# ACNodeShield.net
KiCad netlist of a schematic drawn in EAGLE
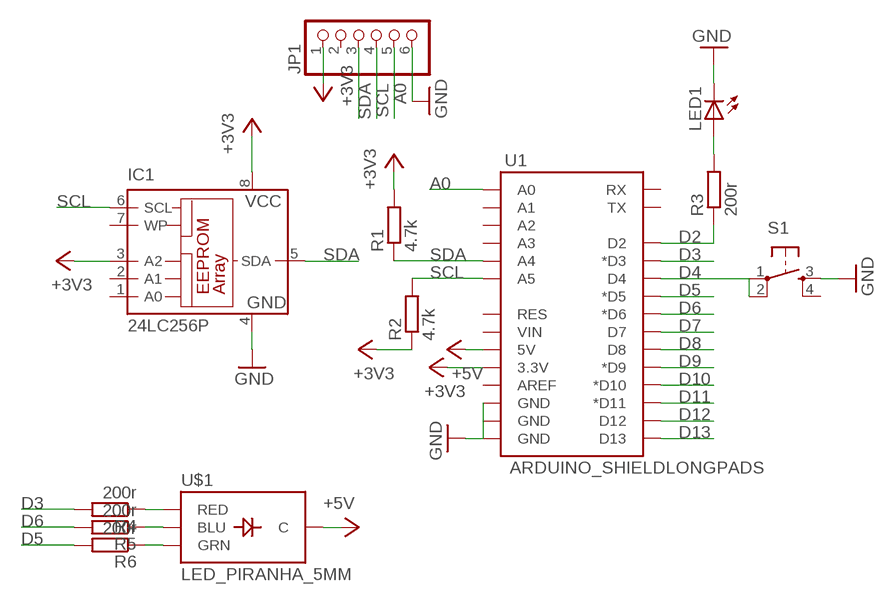
[diagram p0: schematic, sheet 1]

(export (version "E")
  (design (tool "Eeschema 10.0.6"))
  (components
    (comp (ref "IC1")
      (value "24LC256P")
      (footprint "eagle-import:DIL8")
      (fields (field (name "MF") "MICROCHIP") (field (name "MPN") "24LC256-E/P"))
      (libsource (lib "eagle-import") (part "24PLC256"))
    )
    (comp (ref "JP1")
      (value "PINHD-1X6")
      (footprint "eagle-import:1X06")
      (libsource (lib "eagle-import") (part "PINHD-1X6"))
    )
    (comp (ref "LED1")
      (value "LED5MM")
      (footprint "eagle-import:LED5MM")
      (libsource (lib "eagle-import") (part "LED5MM"))
    )
    (comp (ref "R1")
      (value "4.7k")
      (footprint "eagle-import:0204_7")
      (libsource (lib "eagle-import") (part "R-EU_0204/7"))
    )
    (comp (ref "R2")
      (value "4.7k")
      (footprint "eagle-import:0204_7")
      (libsource (lib "eagle-import") (part "R-EU_0204/7"))
    )
    (comp (ref "R3")
      (value "200r")
      (footprint "eagle-import:0204_7")
      (libsource (lib "eagle-import") (part "R-EU_0204/7"))
    )
    (comp (ref "R4")
      (value "200r")
      (footprint "eagle-import:0204_7")
      (libsource (lib "eagle-import") (part "R-EU_0204/7"))
    )
    (comp (ref "R5")
      (value "200r")
      (footprint "eagle-import:0204_7")
      (libsource (lib "eagle-import") (part "R-EU_0204/7"))
    )
    (comp (ref "R6")
      (value "200r")
      (footprint "eagle-import:0204_7")
      (libsource (lib "eagle-import") (part "R-EU_0204/7"))
    )
    (comp (ref "S1")
      (value "TAC_SWITCHPTH")
      (footprint "eagle-import:TACTILE-PTH")
      (libsource (lib "eagle-import") (part "TAC_SWITCHPTH"))
    )
    (comp (ref "U$1")
      (value "LED_PIRANHA_5MM")
      (footprint "eagle-import:LED_PIRANHA_5MM")
      (libsource (lib "eagle-import") (part "LED_PIRANHA_5MM"))
    )
    (comp (ref "U1")
      (value "ARDUINO_SHIELDLONGPADS")
      (footprint "eagle-import:DUEMILANOVE_SHIELD_LONGPADS")
      (libsource (lib "eagle-import") (part "ARDUINO_SHIELDLONGPADS"))
    )
  )
  (nets
    (net (code "1") (name "+3V3") (class "Default")
      (node (ref "IC1") (pin "3") (pinfunction "A2_3") (pintype "input"))
      (node (ref "IC1") (pin "8") (pinfunction "VCC_8") (pintype "power_in"))
      (node (ref "JP1") (pin "1") (pinfunction "1_1") (pintype "passive"))
      (node (ref "R1") (pin "2") (pinfunction "2_2") (pintype "passive"))
      (node (ref "R2") (pin "1") (pinfunction "1_1") (pintype "passive"))
      (node (ref "U1") (pin "3.3V") (pinfunction "3.3V_3.3V") (pintype "bidirectional"))
    )
    (net (code "2") (name "+5V") (class "Default")
      (node (ref "U$1") (pin "-") (pinfunction "C_-") (pintype "bidirectional"))
      (node (ref "U1") (pin "5V") (pinfunction "5V_5V") (pintype "bidirectional"))
    )
    (net (code "3") (name "/A0") (class "Default")
      (node (ref "JP1") (pin "5") (pinfunction "5_5") (pintype "passive"))
      (node (ref "U1") (pin "A0") (pinfunction "A0_A0") (pintype "bidirectional"))
    )
    (net (code "4") (name "/D2") (class "Default")
      (node (ref "R3") (pin "1") (pinfunction "1_1") (pintype "passive"))
      (node (ref "U1") (pin "D2") (pinfunction "D2_D2") (pintype "bidirectional"))
    )
    (net (code "5") (name "/D3") (class "Default")
      (node (ref "R4") (pin "2") (pinfunction "2_2") (pintype "passive"))
      (node (ref "U1") (pin "D3") (pinfunction "*D3_D3") (pintype "bidirectional"))
    )
    (net (code "6") (name "/D4") (class "Default")
      (node (ref "S1") (pin "1") (pinfunction "1_1") (pintype "passive"))
      (node (ref "S1") (pin "2") (pinfunction "2_2") (pintype "passive"))
      (node (ref "U1") (pin "D4") (pinfunction "D4_D4") (pintype "bidirectional"))
    )
    (net (code "7") (name "/D5") (class "Default")
      (node (ref "R6") (pin "2") (pinfunction "2_2") (pintype "passive"))
      (node (ref "U1") (pin "D5") (pinfunction "*D5_D5") (pintype "bidirectional"))
    )
    (net (code "8") (name "/D6") (class "Default")
      (node (ref "R5") (pin "2") (pinfunction "2_2") (pintype "passive"))
      (node (ref "U1") (pin "D6") (pinfunction "*D6_D6") (pintype "bidirectional"))
    )
    (net (code "9") (name "/D7") (class "Default")
      (node (ref "U1") (pin "D7") (pinfunction "D7_D7") (pintype "bidirectional"))
    )
    (net (code "10") (name "/D8") (class "Default")
      (node (ref "U1") (pin "D8") (pinfunction "D8_D8") (pintype "bidirectional"))
    )
    (net (code "11") (name "/D9") (class "Default")
      (node (ref "U1") (pin "D9") (pinfunction "*D9_D9") (pintype "bidirectional"))
    )
    (net (code "12") (name "/D10") (class "Default")
      (node (ref "U1") (pin "D10") (pinfunction "*D10_D10") (pintype "bidirectional"))
    )
    (net (code "13") (name "/D11") (class "Default")
      (node (ref "U1") (pin "D11") (pinfunction "*D11_D11") (pintype "bidirectional"))
    )
    (net (code "14") (name "/D12") (class "Default")
      (node (ref "U1") (pin "D12") (pinfunction "D12_D12") (pintype "bidirectional"))
    )
    (net (code "15") (name "/D13") (class "Default")
      (node (ref "U1") (pin "D13") (pinfunction "D13_D13") (pintype "bidirectional"))
    )
    (net (code "16") (name "/SCL") (class "Default")
      (node (ref "IC1") (pin "6") (pinfunction "SCL_6") (pintype "input"))
      (node (ref "JP1") (pin "4") (pinfunction "4_4") (pintype "passive"))
      (node (ref "R2") (pin "2") (pinfunction "2_2") (pintype "passive"))
      (node (ref "U1") (pin "A5") (pinfunction "A5_A5") (pintype "bidirectional"))
    )
    (net (code "17") (name "/SDA") (class "Default")
      (node (ref "IC1") (pin "5") (pinfunction "SDA_5") (pintype "bidirectional"))
      (node (ref "JP1") (pin "3") (pinfunction "3_3") (pintype "passive"))
      (node (ref "R1") (pin "1") (pinfunction "1_1") (pintype "passive"))
      (node (ref "U1") (pin "A4") (pinfunction "A4_A4") (pintype "bidirectional"))
    )
    (net (code "18") (name "GND") (class "Default")
      (node (ref "IC1") (pin "4") (pinfunction "GND_4") (pintype "power_in"))
      (node (ref "JP1") (pin "6") (pinfunction "6_6") (pintype "passive"))
      (node (ref "LED1") (pin "K") (pinfunction "C_K") (pintype "passive"))
      (node (ref "S1") (pin "3") (pinfunction "3_3") (pintype "passive"))
      (node (ref "U1") (pin "GND@0") (pinfunction "GND_GND@0") (pintype "bidirectional"))
      (node (ref "U1") (pin "GND@1") (pinfunction "GND_GND@1") (pintype "bidirectional"))
      (node (ref "U1") (pin "GND@2") (pinfunction "GND_GND@2") (pintype "bidirectional"))
    )
    (net (code "19") (name "Net-(LED1-PadA)") (class "Default")
      (node (ref "LED1") (pin "A") (pinfunction "A_A") (pintype "passive"))
      (node (ref "R3") (pin "2") (pinfunction "2_2") (pintype "passive"))
    )
    (net (code "20") (name "Net-(U$1-BLU)") (class "Default")
      (node (ref "R5") (pin "1") (pinfunction "1_1") (pintype "passive"))
      (node (ref "U$1") (pin "B") (pinfunction "BLU_B") (pintype "bidirectional"))
    )
    (net (code "21") (name "Net-(U$1-GRN)") (class "Default")
      (node (ref "R6") (pin "1") (pinfunction "1_1") (pintype "passive"))
      (node (ref "U$1") (pin "G") (pinfunction "GRN_G") (pintype "bidirectional"))
    )
    (net (code "22") (name "Net-(U$1-RED)") (class "Default")
      (node (ref "R4") (pin "1") (pinfunction "1_1") (pintype "passive"))
      (node (ref "U$1") (pin "R") (pinfunction "RED_R") (pintype "bidirectional"))
    )
    (net (code "23") (name "unconnected-(IC1-A0-Pad1)") (class "Default")
      (node (ref "IC1") (pin "1") (pinfunction "A0_1") (pintype "input"))
    )
    (net (code "24") (name "unconnected-(IC1-A1-Pad2)") (class "Default")
      (node (ref "IC1") (pin "2") (pinfunction "A1_2") (pintype "input"))
    )
    (net (code "25") (name "unconnected-(IC1-WP-Pad7)") (class "Default")
      (node (ref "IC1") (pin "7") (pinfunction "WP_7") (pintype "input"))
    )
    (net (code "26") (name "unconnected-(JP1-Pad2)") (class "Default")
      (node (ref "JP1") (pin "2") (pinfunction "2_2") (pintype "passive"))
    )
    (net (code "27") (name "unconnected-(S1-Pad4)") (class "Default")
      (node (ref "S1") (pin "4") (pinfunction "4_4") (pintype "passive"))
    )
    (net (code "28") (name "unconnected-(U1-PadA1)") (class "Default")
      (node (ref "U1") (pin "A1") (pinfunction "A1_A1") (pintype "bidirectional"))
    )
    (net (code "29") (name "unconnected-(U1-PadA2)") (class "Default")
      (node (ref "U1") (pin "A2") (pinfunction "A2_A2") (pintype "bidirectional"))
    )
    (net (code "30") (name "unconnected-(U1-PadA3)") (class "Default")
      (node (ref "U1") (pin "A3") (pinfunction "A3_A3") (pintype "bidirectional"))
    )
    (net (code "31") (name "unconnected-(U1-PadAREF)") (class "Default")
      (node (ref "U1") (pin "AREF") (pinfunction "AREF_AREF") (pintype "bidirectional"))
    )
    (net (code "32") (name "unconnected-(U1-PadRES)") (class "Default")
      (node (ref "U1") (pin "RES") (pinfunction "RES_RES") (pintype "bidirectional"))
    )
    (net (code "33") (name "unconnected-(U1-PadRX)") (class "Default")
      (node (ref "U1") (pin "RX") (pinfunction "RX_RX") (pintype "bidirectional"))
    )
    (net (code "34") (name "unconnected-(U1-PadTX)") (class "Default")
      (node (ref "U1") (pin "TX") (pinfunction "TX_TX") (pintype "bidirectional"))
    )
    (net (code "35") (name "unconnected-(U1-PadVIN)") (class "Default")
      (node (ref "U1") (pin "VIN") (pinfunction "VIN_VIN") (pintype "bidirectional"))
    )
  )
)
